# LOGIC.net
KiCad netlist of a schematic drawn in Altium Designer
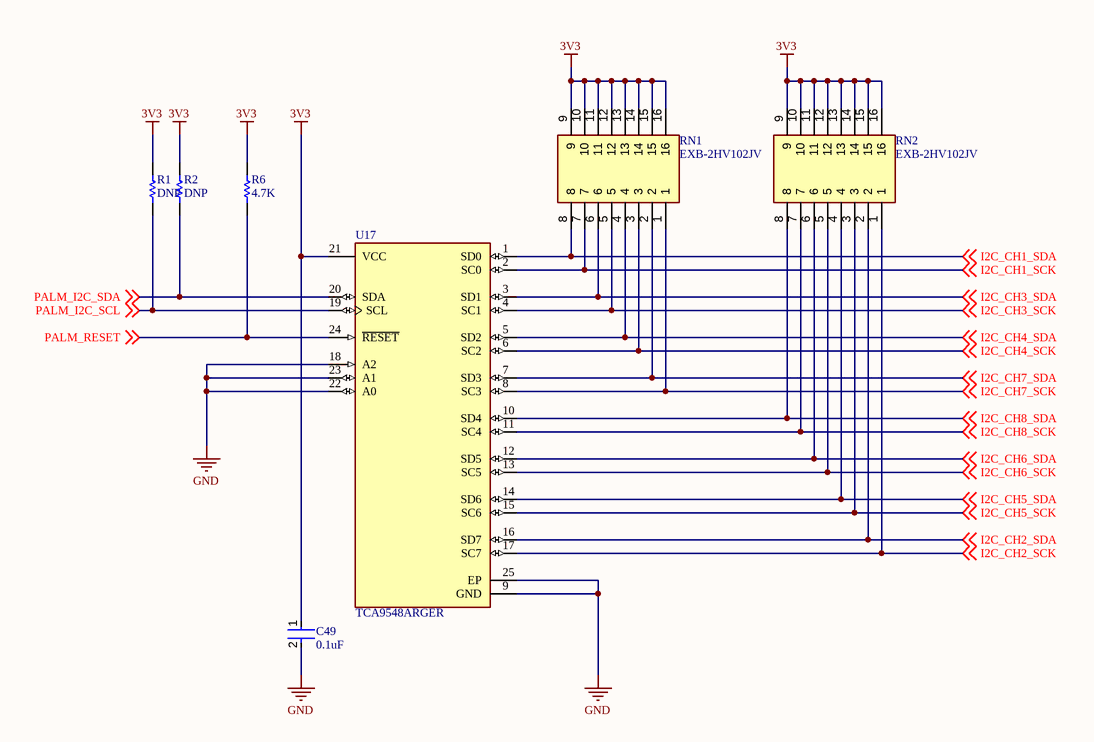
[diagram p0: LOGIC.SchDoc]

(export (version "E")
  (design (tool "Eeschema 10.0.6"))
  (components
    (comp (ref "C49")
      (value "0.1uF")
      (footprint "FP-GRM15-MFG")
      (description "CAP CER 0.1UF 16V X7R 0402")
      (fields (field (name "MANUFACTURER PART NUMBER") "GRM155R71C104KA88D") (field (name "TOLERANCE") "10%"))
      (libsource (lib "Altium Content Vault") (part "236180d848d6139a670b325ea6854c9"))
    )
    (comp (ref "R1")
      (value "DNP")
      (footprint "RESC1005X40X25LL05T10")
      (fields (field (name "PART NUMBER") "RC0402JR-071KL") (field (name "MANUFACTURER") "Yageo / Phycomp"))
      (libsource (lib "Altium Content Vault") (part "RES"))
    )
    (comp (ref "R2")
      (value "DNP")
      (footprint "RESC1005X40X25LL05T10")
      (fields (field (name "PART NUMBER") "RC0402JR-071KL") (field (name "MANUFACTURER") "Yageo / Phycomp"))
      (libsource (lib "Altium Content Vault") (part "RES"))
    )
    (comp (ref "R6")
      (value "4.7K")
      (footprint "RESC1005X40X25LL05T05")
      (description "Chip Resistor, 4.7 KOhm, +/- 1%, 0.1 W, -55 to 155 degC, 0402 (1005 Metric), RoHS, Tape and Reel")
      (fields (field (name "TOLERANCE") "1%") (field (name "PARTNUMBER") "ERJ-2RKF4701X"))
      (libsource (lib "Altium Content Vault") (part "RES-2"))
    )
    (comp (ref "RN1")
      (value "EXB-2HV102JV")
      (footprint "SamacSys:EXB2HV102JV")
      (description "Resistor Network")
      (fields (field (name "MOUSER PART NUMBER") "667-EXB-2HV102JV"))
      (libsource (lib "*") (part "EXB-2HV102JV"))
    )
    (comp (ref "RN2")
      (value "EXB-2HV102JV")
      (footprint "SamacSys:EXB2HV102JV")
      (description "Resistor Network")
      (fields (field (name "MOUSER PART NUMBER") "667-EXB-2HV102JV"))
      (libsource (lib "*") (part "EXB-2HV102JV"))
    )
    (comp (ref "U17")
      (value "TCA9548ARGER")
      (footprint "FP-RGE0024C-MFG")
      (description "IC I2C SW 8CH W/RESET 24VQFN")
      (libsource (lib "Altium Content Vault") (part "87ad65078381ad6992a0152d7f2ce2c"))
    )
  )
  (nets
    (net (code "1") (name "3V3") (class "Default")
      (node (ref "C49") (pin "1") (pinfunction "1_1") (pintype "passive"))
      (node (ref "R1") (pin "2") (pinfunction "2_2") (pintype "passive"))
      (node (ref "R2") (pin "2") (pinfunction "2_2") (pintype "passive"))
      (node (ref "R6") (pin "2") (pinfunction "2_2") (pintype "passive"))
      (node (ref "RN1") (pin "10") (pinfunction "10_10") (pintype "passive"))
      (node (ref "RN1") (pin "11") (pinfunction "11_11") (pintype "passive"))
      (node (ref "RN1") (pin "12") (pinfunction "12_12") (pintype "passive"))
      (node (ref "RN1") (pin "13") (pinfunction "13_13") (pintype "passive"))
      (node (ref "RN1") (pin "14") (pinfunction "14_14") (pintype "passive"))
      (node (ref "RN1") (pin "15") (pinfunction "15_15") (pintype "passive"))
      (node (ref "RN1") (pin "16") (pinfunction "16_16") (pintype "passive"))
      (node (ref "RN1") (pin "9") (pinfunction "9_9") (pintype "passive"))
      (node (ref "RN2") (pin "10") (pinfunction "10_10") (pintype "passive"))
      (node (ref "RN2") (pin "11") (pinfunction "11_11") (pintype "passive"))
      (node (ref "RN2") (pin "12") (pinfunction "12_12") (pintype "passive"))
      (node (ref "RN2") (pin "13") (pinfunction "13_13") (pintype "passive"))
      (node (ref "RN2") (pin "14") (pinfunction "14_14") (pintype "passive"))
      (node (ref "RN2") (pin "15") (pinfunction "15_15") (pintype "passive"))
      (node (ref "RN2") (pin "16") (pinfunction "16_16") (pintype "passive"))
      (node (ref "RN2") (pin "9") (pinfunction "9_9") (pintype "passive"))
      (node (ref "U17") (pin "21") (pinfunction "VCC_21") (pintype "power_in"))
    )
    (net (code "2") (name "GND") (class "Default")
      (node (ref "C49") (pin "2") (pinfunction "2_2") (pintype "passive"))
      (node (ref "U17") (pin "18") (pinfunction "A2_18") (pintype "input"))
      (node (ref "U17") (pin "22") (pinfunction "A0_22") (pintype "bidirectional"))
      (node (ref "U17") (pin "23") (pinfunction "A1_23") (pintype "bidirectional"))
      (node (ref "U17") (pin "25") (pinfunction "EP_25") (pintype "power_in"))
      (node (ref "U17") (pin "9") (pinfunction "GND_9") (pintype "power_in"))
    )
    (net (code "3") (name "I2C_CH1_SCK") (class "Default")
      (node (ref "RN1") (pin "7") (pinfunction "7_7") (pintype "passive"))
      (node (ref "U17") (pin "2") (pinfunction "SC0_2") (pintype "bidirectional"))
    )
    (net (code "4") (name "I2C_CH1_SDA") (class "Default")
      (node (ref "RN1") (pin "8") (pinfunction "8_8") (pintype "passive"))
      (node (ref "U17") (pin "1") (pinfunction "SD0_1") (pintype "bidirectional"))
    )
    (net (code "5") (name "I2C_CH2_SCK") (class "Default")
      (node (ref "RN2") (pin "1") (pinfunction "1_1") (pintype "passive"))
      (node (ref "U17") (pin "17") (pinfunction "SC7_17") (pintype "bidirectional"))
    )
    (net (code "6") (name "I2C_CH2_SDA") (class "Default")
      (node (ref "RN2") (pin "2") (pinfunction "2_2") (pintype "passive"))
      (node (ref "U17") (pin "16") (pinfunction "SD7_16") (pintype "bidirectional"))
    )
    (net (code "7") (name "I2C_CH3_SCK") (class "Default")
      (node (ref "RN1") (pin "5") (pinfunction "5_5") (pintype "passive"))
      (node (ref "U17") (pin "4") (pinfunction "SC1_4") (pintype "bidirectional"))
    )
    (net (code "8") (name "I2C_CH3_SDA") (class "Default")
      (node (ref "RN1") (pin "6") (pinfunction "6_6") (pintype "passive"))
      (node (ref "U17") (pin "3") (pinfunction "SD1_3") (pintype "bidirectional"))
    )
    (net (code "9") (name "I2C_CH4_SCK") (class "Default")
      (node (ref "RN1") (pin "3") (pinfunction "3_3") (pintype "passive"))
      (node (ref "U17") (pin "6") (pinfunction "SC2_6") (pintype "bidirectional"))
    )
    (net (code "10") (name "I2C_CH4_SDA") (class "Default")
      (node (ref "RN1") (pin "4") (pinfunction "4_4") (pintype "passive"))
      (node (ref "U17") (pin "5") (pinfunction "SD2_5") (pintype "bidirectional"))
    )
    (net (code "11") (name "I2C_CH5_SCK") (class "Default")
      (node (ref "RN2") (pin "3") (pinfunction "3_3") (pintype "passive"))
      (node (ref "U17") (pin "15") (pinfunction "SC6_15") (pintype "bidirectional"))
    )
    (net (code "12") (name "I2C_CH5_SDA") (class "Default")
      (node (ref "RN2") (pin "4") (pinfunction "4_4") (pintype "passive"))
      (node (ref "U17") (pin "14") (pinfunction "SD6_14") (pintype "bidirectional"))
    )
    (net (code "13") (name "I2C_CH6_SCK") (class "Default")
      (node (ref "RN2") (pin "5") (pinfunction "5_5") (pintype "passive"))
      (node (ref "U17") (pin "13") (pinfunction "SC5_13") (pintype "bidirectional"))
    )
    (net (code "14") (name "I2C_CH6_SDA") (class "Default")
      (node (ref "RN2") (pin "6") (pinfunction "6_6") (pintype "passive"))
      (node (ref "U17") (pin "12") (pinfunction "SD5_12") (pintype "bidirectional"))
    )
    (net (code "15") (name "I2C_CH7_SCK") (class "Default")
      (node (ref "RN1") (pin "1") (pinfunction "1_1") (pintype "passive"))
      (node (ref "U17") (pin "8") (pinfunction "SC3_8") (pintype "bidirectional"))
    )
    (net (code "16") (name "I2C_CH7_SDA") (class "Default")
      (node (ref "RN1") (pin "2") (pinfunction "2_2") (pintype "passive"))
      (node (ref "U17") (pin "7") (pinfunction "SD3_7") (pintype "bidirectional"))
    )
    (net (code "17") (name "I2C_CH8_SCK") (class "Default")
      (node (ref "RN2") (pin "7") (pinfunction "7_7") (pintype "passive"))
      (node (ref "U17") (pin "11") (pinfunction "SC4_11") (pintype "bidirectional"))
    )
    (net (code "18") (name "I2C_CH8_SDA") (class "Default")
      (node (ref "RN2") (pin "8") (pinfunction "8_8") (pintype "passive"))
      (node (ref "U17") (pin "10") (pinfunction "SD4_10") (pintype "bidirectional"))
    )
    (net (code "19") (name "PALM_I2C_SCL") (class "Default")
      (node (ref "R1") (pin "1") (pinfunction "1_1") (pintype "passive"))
      (node (ref "U17") (pin "19") (pinfunction "SCL_19") (pintype "bidirectional"))
    )
    (net (code "20") (name "PALM_I2C_SDA") (class "Default")
      (node (ref "R2") (pin "1") (pinfunction "1_1") (pintype "passive"))
      (node (ref "U17") (pin "20") (pinfunction "SDA_20") (pintype "bidirectional"))
    )
    (net (code "21") (name "PALM_RESET") (class "Default")
      (node (ref "R6") (pin "1") (pinfunction "1_1") (pintype "passive"))
      (node (ref "U17") (pin "24") (pinfunction "~{RESET}_24") (pintype "input"))
    )
  )
)
